# Receiver.net
KiCad netlist of a schematic drawn in EAGLE
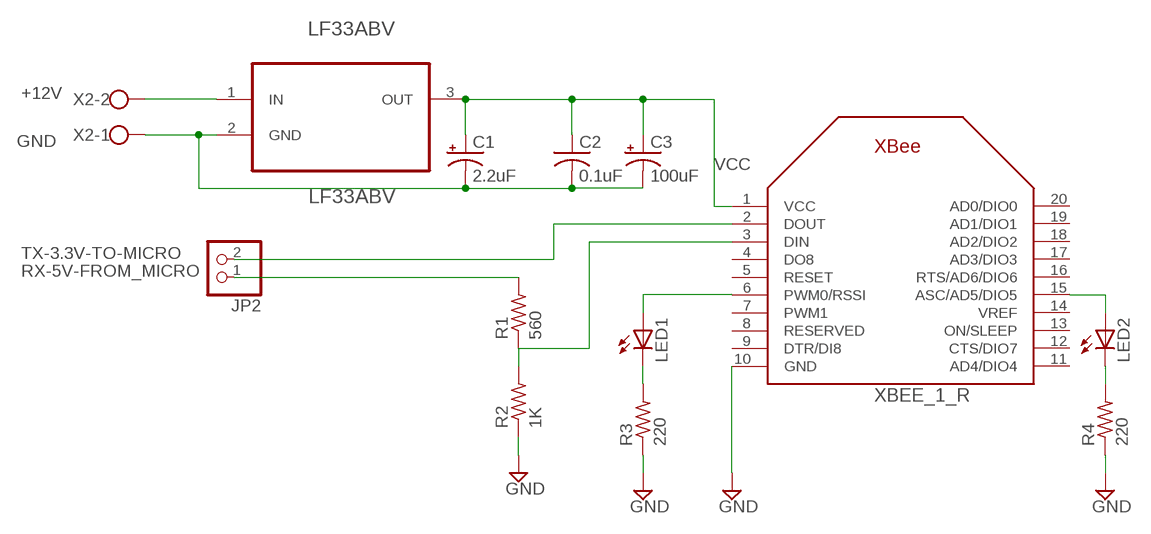
[diagram p0: schematic, sheet 1]

(export (version "E")
  (design (tool "Eeschema 10.0.6"))
  (components
    (comp (ref "C1")
      (value "2.2uF")
      (footprint "eagle-import:CPOL-RADIAL-10UF-25V")
      (libsource (lib "eagle-import") (part "CAP_POLPTH2"))
    )
    (comp (ref "C2")
      (value "0.1uF")
      (footprint "eagle-import:C025-024X044")
      (libsource (lib "eagle-import") (part "C-US025-024X044"))
    )
    (comp (ref "C3")
      (value "100uF")
      (footprint "eagle-import:CPOL-RADIAL-100UF-25V")
      (libsource (lib "eagle-import") (part "CAP_POLPTH1"))
    )
    (comp (ref "JP2")
      (value "PINHD-1X2")
      (footprint "eagle-import:1X02")
      (libsource (lib "eagle-import") (part "PINHD-1X2"))
    )
    (comp (ref "LED1")
      (value "LED5MM")
      (footprint "eagle-import:LED5MM")
      (libsource (lib "eagle-import") (part "LED5MM"))
    )
    (comp (ref "LED2")
      (value "LED5MM")
      (footprint "eagle-import:LED5MM")
      (libsource (lib "eagle-import") (part "LED5MM"))
    )
    (comp (ref "LF33ABV")
      (value "LF33ABV")
      (footprint "eagle-import:TO254P450X1020X1935-3P")
      (libsource (lib "eagle-import") (part "LF33ABV"))
    )
    (comp (ref "R1")
      (value "560")
      (footprint "eagle-import:0207_10")
      (libsource (lib "eagle-import") (part "R-US_0207/10"))
    )
    (comp (ref "R2")
      (value "1K")
      (footprint "eagle-import:0207_10")
      (libsource (lib "eagle-import") (part "R-US_0207/10"))
    )
    (comp (ref "R3")
      (value "220")
      (footprint "eagle-import:0207_10")
      (libsource (lib "eagle-import") (part "resistor_R-US_0207/10"))
    )
    (comp (ref "R4")
      (value "220")
      (footprint "eagle-import:0207_10")
      (libsource (lib "eagle-import") (part "resistor_R-US_0207/10"))
    )
    (comp (ref "X2")
      (value "W237-102")
      (footprint "eagle-import:W237-102")
      (fields (field (name "MPN") "237-102"))
      (libsource (lib "eagle-import") (part "W237-102"))
    )
    (comp (ref "XBEE_1_R")
      (value "XBEE")
      (footprint "eagle-import:XBEE")
      (libsource (lib "eagle-import") (part "XBEE"))
    )
  )
  (nets
    (net (code "1") (name "/+12V") (class "Default")
      (node (ref "LF33ABV") (pin "1") (pinfunction "IN_1") (pintype "input"))
      (node (ref "X2") (pin "2") (pinfunction "KL_2") (pintype "passive"))
    )
    (net (code "2") (name "/RX-5V-FROM_MICRO") (class "Default")
      (node (ref "JP2") (pin "1") (pinfunction "1_1") (pintype "passive"))
      (node (ref "R1") (pin "2") (pinfunction "2_2") (pintype "passive"))
    )
    (net (code "3") (name "/TX-3.3V-TO-MICRO") (class "Default")
      (node (ref "JP2") (pin "2") (pinfunction "2_2") (pintype "passive"))
      (node (ref "XBEE_1_R") (pin "2") (pinfunction "DOUT_2") (pintype "output"))
    )
    (net (code "4") (name "/VCC") (class "Default")
      (node (ref "C1") (pin "1") (pinfunction "+_1") (pintype "passive"))
      (node (ref "C2") (pin "1") (pinfunction "1_1") (pintype "passive"))
      (node (ref "C3") (pin "1") (pinfunction "+_1") (pintype "passive"))
      (node (ref "LF33ABV") (pin "3") (pinfunction "OUT_3") (pintype "output"))
      (node (ref "XBEE_1_R") (pin "1") (pinfunction "VCC_1") (pintype "power_in"))
    )
    (net (code "5") (name "GND") (class "Default")
      (node (ref "C1") (pin "2") (pinfunction "-_2") (pintype "passive"))
      (node (ref "C2") (pin "2") (pinfunction "2_2") (pintype "passive"))
      (node (ref "C3") (pin "2") (pinfunction "-_2") (pintype "passive"))
      (node (ref "LF33ABV") (pin "2") (pinfunction "GND_2") (pintype "passive"))
      (node (ref "R2") (pin "1") (pinfunction "1_1") (pintype "passive"))
      (node (ref "R3") (pin "1") (pinfunction "1_1") (pintype "passive"))
      (node (ref "R4") (pin "1") (pinfunction "1_1") (pintype "passive"))
      (node (ref "X2") (pin "1") (pinfunction "KL_1") (pintype "passive"))
      (node (ref "XBEE_1_R") (pin "10") (pinfunction "GND_10") (pintype "power_in"))
    )
    (net (code "6") (name "Net-(LED1-C)") (class "Default")
      (node (ref "LED1") (pin "K") (pinfunction "C_K") (pintype "passive"))
      (node (ref "R3") (pin "2") (pinfunction "2_2") (pintype "passive"))
    )
    (net (code "7") (name "Net-(LED2-C)") (class "Default")
      (node (ref "LED2") (pin "K") (pinfunction "C_K") (pintype "passive"))
      (node (ref "R4") (pin "2") (pinfunction "2_2") (pintype "passive"))
    )
    (net (code "8") (name "Net-(XBEE_1_R-ASC{slash}AD5{slash}DIO5)") (class "Default")
      (node (ref "LED2") (pin "A") (pinfunction "A_A") (pintype "passive"))
      (node (ref "XBEE_1_R") (pin "15") (pinfunction "ASC/AD5/DIO5_15") (pintype "bidirectional"))
    )
    (net (code "9") (name "Net-(XBEE_1_R-DIN)") (class "Default")
      (node (ref "R1") (pin "1") (pinfunction "1_1") (pintype "passive"))
      (node (ref "R2") (pin "2") (pinfunction "2_2") (pintype "passive"))
      (node (ref "XBEE_1_R") (pin "3") (pinfunction "DIN_3") (pintype "input"))
    )
    (net (code "10") (name "Net-(XBEE_1_R-PWM0{slash}RSSI)") (class "Default")
      (node (ref "LED1") (pin "A") (pinfunction "A_A") (pintype "passive"))
      (node (ref "XBEE_1_R") (pin "6") (pinfunction "PWM0/RSSI_6") (pintype "output"))
    )
    (net (code "11") (name "unconnected-(XBEE_1_R-AD0{slash}DIO0-Pad20)") (class "Default")
      (node (ref "XBEE_1_R") (pin "20") (pinfunction "AD0/DIO0_20") (pintype "bidirectional"))
    )
    (net (code "12") (name "unconnected-(XBEE_1_R-AD1{slash}DIO1-Pad19)") (class "Default")
      (node (ref "XBEE_1_R") (pin "19") (pinfunction "AD1/DIO1_19") (pintype "bidirectional"))
    )
    (net (code "13") (name "unconnected-(XBEE_1_R-AD2{slash}DIO2-Pad18)") (class "Default")
      (node (ref "XBEE_1_R") (pin "18") (pinfunction "AD2/DIO2_18") (pintype "bidirectional"))
    )
    (net (code "14") (name "unconnected-(XBEE_1_R-AD3{slash}DIO3-Pad17)") (class "Default")
      (node (ref "XBEE_1_R") (pin "17") (pinfunction "AD3/DIO3_17") (pintype "bidirectional"))
    )
    (net (code "15") (name "unconnected-(XBEE_1_R-AD4{slash}DIO4-Pad11)") (class "Default")
      (node (ref "XBEE_1_R") (pin "11") (pinfunction "AD4/DIO4_11") (pintype "bidirectional"))
    )
    (net (code "16") (name "unconnected-(XBEE_1_R-CTS{slash}DIO7-Pad12)") (class "Default")
      (node (ref "XBEE_1_R") (pin "12") (pinfunction "CTS/DIO7_12") (pintype "bidirectional"))
    )
    (net (code "17") (name "unconnected-(XBEE_1_R-DO8-Pad4)") (class "Default")
      (node (ref "XBEE_1_R") (pin "4") (pinfunction "DO8_4") (pintype "output"))
    )
    (net (code "18") (name "unconnected-(XBEE_1_R-DTR{slash}DI8-Pad9)") (class "Default")
      (node (ref "XBEE_1_R") (pin "9") (pinfunction "DTR/DI8_9") (pintype "input"))
    )
    (net (code "19") (name "unconnected-(XBEE_1_R-ON{slash}SLEEP-Pad13)") (class "Default")
      (node (ref "XBEE_1_R") (pin "13") (pinfunction "ON/SLEEP_13") (pintype "output"))
    )
    (net (code "20") (name "unconnected-(XBEE_1_R-PWM1-Pad7)") (class "Default")
      (node (ref "XBEE_1_R") (pin "7") (pinfunction "PWM1_7") (pintype "output"))
    )
    (net (code "21") (name "unconnected-(XBEE_1_R-RESERVED-Pad8)") (class "Default")
      (node (ref "XBEE_1_R") (pin "8") (pinfunction "RESERVED_8") (pintype "no_connect"))
    )
    (net (code "22") (name "unconnected-(XBEE_1_R-RESET-Pad5)") (class "Default")
      (node (ref "XBEE_1_R") (pin "5") (pinfunction "RESET_5") (pintype "input"))
    )
    (net (code "23") (name "unconnected-(XBEE_1_R-RTS{slash}AD6{slash}DIO6-Pad16)") (class "Default")
      (node (ref "XBEE_1_R") (pin "16") (pinfunction "RTS/AD6/DIO6_16") (pintype "bidirectional"))
    )
    (net (code "24") (name "unconnected-(XBEE_1_R-VREF-Pad14)") (class "Default")
      (node (ref "XBEE_1_R") (pin "14") (pinfunction "VREF_14") (pintype "input"))
    )
  )
)
